# PLCC-RP2350B-PSRAM.net
KiCad netlist of a schematic drawn in Altium Designer
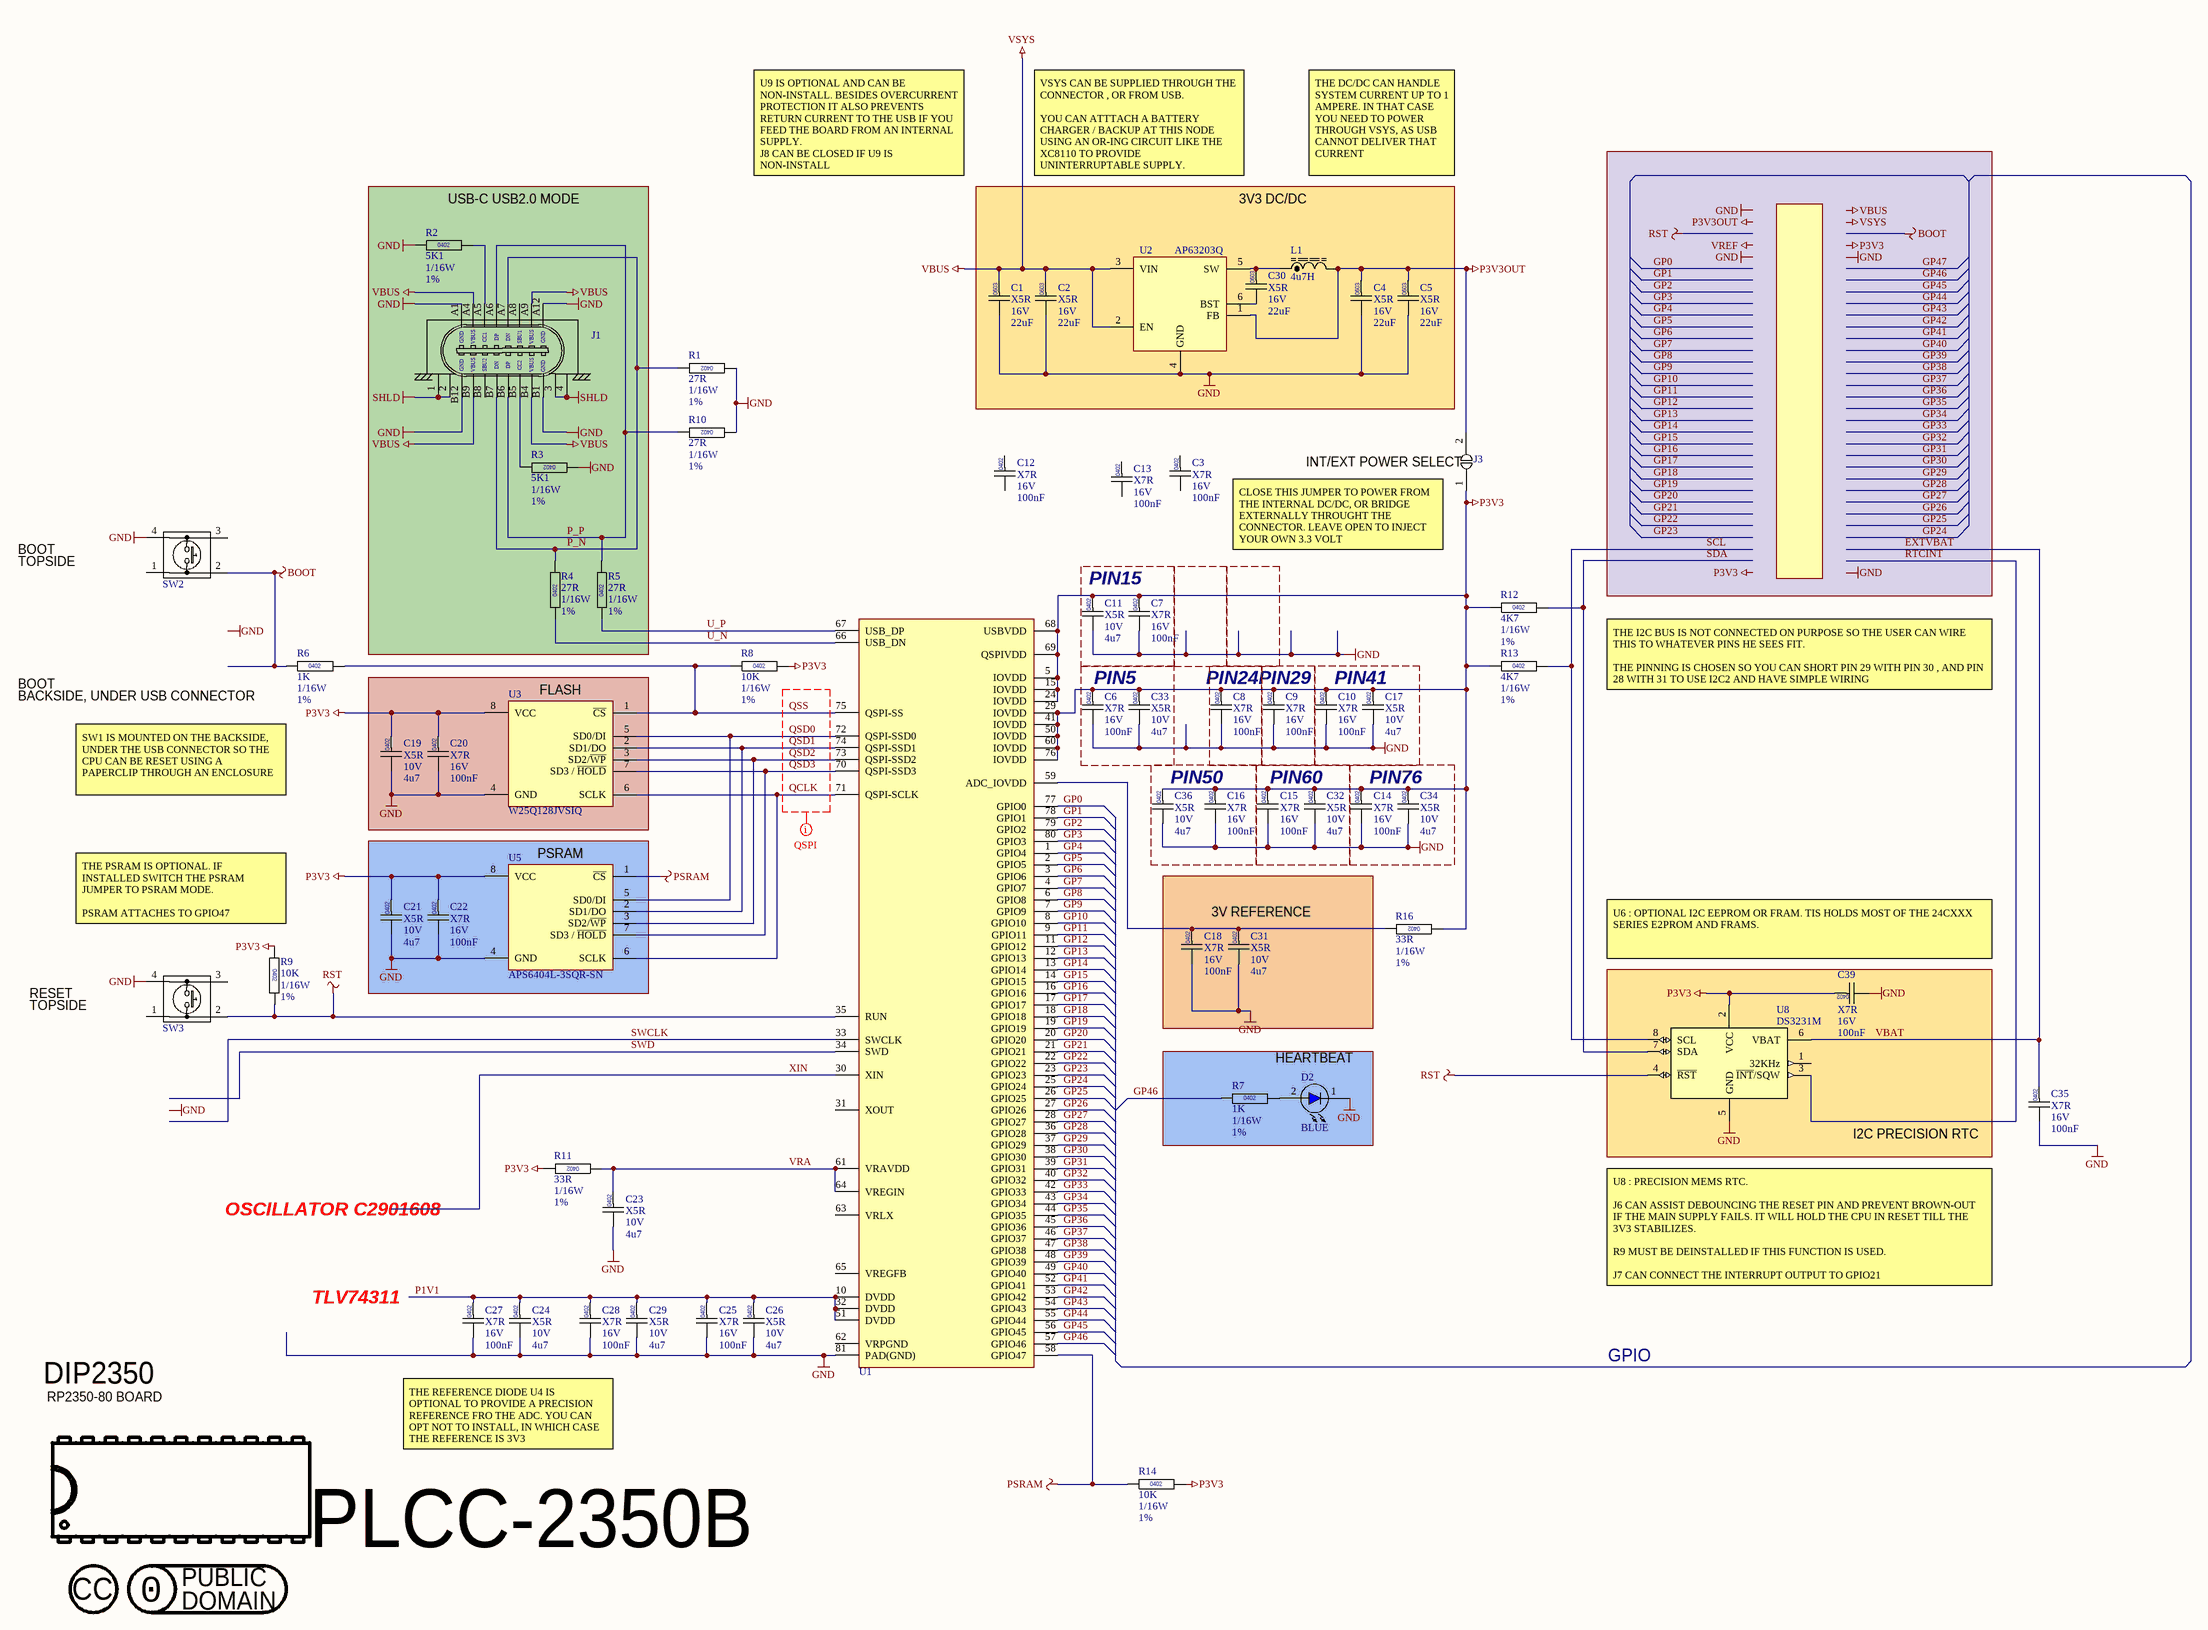
[diagram p0: PLCC-RP2350B-PSRAM.SchDoc]

(export (version "E")
  (design (tool "Eeschema 10.0.6"))
  (components
    (comp (ref "C1")
      (value "CAP0603")
      (footprint "CAPC0603")
      (description "CAPACITOR,CERAMIC,22uF,16V,X5R,0603")
      (fields
        (field (name "DIELECTRIC") "X5R")
        (field (name "VOLTAGE") "16V")
        (field (name "CAPACITANCE") "22uF")
      )
      (libsource (lib "CAPACITORS") (part "CAPC-0603-22uF-16V-X5R"))
    )
    (comp (ref "C2")
      (value "CAP0603")
      (footprint "CAPC0603")
      (description "CAPACITOR,CERAMIC,22uF,16V,X5R,0603")
      (fields
        (field (name "DIELECTRIC") "X5R")
        (field (name "VOLTAGE") "16V")
        (field (name "CAPACITANCE") "22uF")
      )
      (libsource (lib "CAPACITORS") (part "CAPC-0603-22uF-16V-X5R"))
    )
    (comp (ref "C3")
      (value "CAP0402")
      (footprint "CAPC0402")
      (description "CAPACITOR,CERAMIC,100nF,16V,X7R,0402")
      (fields
        (field (name "DIELECTRIC") "X7R")
        (field (name "VOLTAGE") "16V")
        (field (name "CAPACITANCE") "100nF")
      )
      (libsource (lib "CAPACITORS") (part "CAPC-0402-100nF-16V-X7R"))
    )
    (comp (ref "C4")
      (value "CAP0603")
      (footprint "CAPC0603")
      (description "CAPACITOR,CERAMIC,22uF,16V,X5R,0603")
      (fields
        (field (name "DIELECTRIC") "X5R")
        (field (name "VOLTAGE") "16V")
        (field (name "CAPACITANCE") "22uF")
      )
      (libsource (lib "CAPACITORS") (part "CAPC-0603-22uF-16V-X5R"))
    )
    (comp (ref "C5")
      (value "CAP0603")
      (footprint "CAPC0603")
      (description "CAPACITOR,CERAMIC,22uF,16V,X5R,0603")
      (fields
        (field (name "DIELECTRIC") "X5R")
        (field (name "VOLTAGE") "16V")
        (field (name "CAPACITANCE") "22uF")
      )
      (libsource (lib "CAPACITORS") (part "CAPC-0603-22uF-16V-X5R"))
    )
    (comp (ref "C6")
      (value "CAP0402")
      (footprint "CAPC0402")
      (description "CAPACITOR,CERAMIC,100nF,16V,X7R,0402")
      (fields
        (field (name "DIELECTRIC") "X7R")
        (field (name "VOLTAGE") "16V")
        (field (name "CAPACITANCE") "100nF")
      )
      (libsource (lib "CAPACITORS") (part "CAPC-0402-100nF-16V-X7R"))
    )
    (comp (ref "C7")
      (value "CAP0402")
      (footprint "CAPC0402")
      (description "CAPACITOR,CERAMIC,100nF,16V,X7R,0402")
      (fields
        (field (name "DIELECTRIC") "X7R")
        (field (name "VOLTAGE") "16V")
        (field (name "CAPACITANCE") "100nF")
      )
      (libsource (lib "CAPACITORS") (part "CAPC-0402-100nF-16V-X7R"))
    )
    (comp (ref "C8")
      (value "CAP0402")
      (footprint "CAPC0402")
      (description "CAPACITOR,CERAMIC,100nF,16V,X7R,0402")
      (fields
        (field (name "DIELECTRIC") "X7R")
        (field (name "VOLTAGE") "16V")
        (field (name "CAPACITANCE") "100nF")
      )
      (libsource (lib "CAPACITORS") (part "CAPC-0402-100nF-16V-X7R"))
    )
    (comp (ref "C9")
      (value "CAP0402")
      (footprint "CAPC0402")
      (description "CAPACITOR,CERAMIC,100nF,16V,X7R,0402")
      (fields
        (field (name "DIELECTRIC") "X7R")
        (field (name "VOLTAGE") "16V")
        (field (name "CAPACITANCE") "100nF")
      )
      (libsource (lib "CAPACITORS") (part "CAPC-0402-100nF-16V-X7R"))
    )
    (comp (ref "C10")
      (value "CAP0402")
      (footprint "CAPC0402")
      (description "CAPACITOR,CERAMIC,100nF,16V,X7R,0402")
      (fields
        (field (name "DIELECTRIC") "X7R")
        (field (name "VOLTAGE") "16V")
        (field (name "CAPACITANCE") "100nF")
      )
      (libsource (lib "CAPACITORS") (part "CAPC-0402-100nF-16V-X7R"))
    )
    (comp (ref "C11")
      (value "CAP0402")
      (footprint "CAPC0402")
      (description "CAPACITOR,CERAMIC,4u7,10V,X5R,0402")
      (fields
        (field (name "DIELECTRIC") "X5R")
        (field (name "VOLTAGE") "10V")
        (field (name "CAPACITANCE") "4u7")
      )
      (libsource (lib "CAPACITORS") (part "CAPC-0402-4u7-10V-X5R"))
    )
    (comp (ref "C12")
      (value "CAP0402")
      (footprint "CAPC0402")
      (description "CAPACITOR,CERAMIC,100nF,16V,X7R,0402")
      (fields
        (field (name "DIELECTRIC") "X7R")
        (field (name "VOLTAGE") "16V")
        (field (name "CAPACITANCE") "100nF")
      )
      (libsource (lib "CAPACITORS") (part "CAPC-0402-100nF-16V-X7R"))
    )
    (comp (ref "C13")
      (value "CAP0402")
      (footprint "CAPC0402")
      (description "CAPACITOR,CERAMIC,100nF,16V,X7R,0402")
      (fields
        (field (name "DIELECTRIC") "X7R")
        (field (name "VOLTAGE") "16V")
        (field (name "CAPACITANCE") "100nF")
      )
      (libsource (lib "CAPACITORS") (part "CAPC-0402-100nF-16V-X7R"))
    )
    (comp (ref "C14")
      (value "CAP0402")
      (footprint "CAPC0402")
      (description "CAPACITOR,CERAMIC,100nF,16V,X7R,0402")
      (fields
        (field (name "DIELECTRIC") "X7R")
        (field (name "VOLTAGE") "16V")
        (field (name "CAPACITANCE") "100nF")
      )
      (libsource (lib "CAPACITORS") (part "CAPC-0402-100nF-16V-X7R"))
    )
    (comp (ref "C15")
      (value "CAP0402")
      (footprint "CAPC0402")
      (description "CAPACITOR,CERAMIC,100nF,16V,X7R,0402")
      (fields
        (field (name "DIELECTRIC") "X7R")
        (field (name "VOLTAGE") "16V")
        (field (name "CAPACITANCE") "100nF")
      )
      (libsource (lib "CAPACITORS") (part "CAPC-0402-100nF-16V-X7R"))
    )
    (comp (ref "C16")
      (value "CAP0402")
      (footprint "CAPC0402")
      (description "CAPACITOR,CERAMIC,100nF,16V,X7R,0402")
      (fields
        (field (name "DIELECTRIC") "X7R")
        (field (name "VOLTAGE") "16V")
        (field (name "CAPACITANCE") "100nF")
      )
      (libsource (lib "CAPACITORS") (part "CAPC-0402-100nF-16V-X7R"))
    )
    (comp (ref "C17")
      (value "CAP0402")
      (footprint "CAPC0402")
      (description "CAPACITOR,CERAMIC,4u7,10V,X5R,0402")
      (fields
        (field (name "DIELECTRIC") "X5R")
        (field (name "VOLTAGE") "10V")
        (field (name "CAPACITANCE") "4u7")
      )
      (libsource (lib "CAPACITORS") (part "CAPC-0402-4u7-10V-X5R"))
    )
    (comp (ref "C18")
      (value "CAP0402")
      (footprint "CAPC0402")
      (description "CAPACITOR,CERAMIC,100nF,16V,X7R,0402")
      (fields
        (field (name "DIELECTRIC") "X7R")
        (field (name "VOLTAGE") "16V")
        (field (name "CAPACITANCE") "100nF")
      )
      (libsource (lib "CAPACITORS") (part "CAPC-0402-100nF-16V-X7R"))
    )
    (comp (ref "C19")
      (value "CAP0402")
      (footprint "CAPC0402")
      (description "CAPACITOR,CERAMIC,4u7,10V,X5R,0402")
      (fields
        (field (name "DIELECTRIC") "X5R")
        (field (name "VOLTAGE") "10V")
        (field (name "CAPACITANCE") "4u7")
      )
      (libsource (lib "CAPACITORS") (part "CAPC-0402-4u7-10V-X5R"))
    )
    (comp (ref "C20")
      (value "CAP0402")
      (footprint "CAPC0402")
      (description "CAPACITOR,CERAMIC,100nF,16V,X7R,0402")
      (fields
        (field (name "DIELECTRIC") "X7R")
        (field (name "VOLTAGE") "16V")
        (field (name "CAPACITANCE") "100nF")
      )
      (libsource (lib "CAPACITORS") (part "CAPC-0402-100nF-16V-X7R"))
    )
    (comp (ref "C21")
      (value "CAP0402")
      (footprint "CAPC0402")
      (description "CAPACITOR,CERAMIC,4u7,10V,X5R,0402")
      (fields
        (field (name "DIELECTRIC") "X5R")
        (field (name "VOLTAGE") "10V")
        (field (name "CAPACITANCE") "4u7")
      )
      (libsource (lib "CAPACITORS") (part "CAPC-0402-4u7-10V-X5R"))
    )
    (comp (ref "C22")
      (value "CAP0402")
      (footprint "CAPC0402")
      (description "CAPACITOR,CERAMIC,100nF,16V,X7R,0402")
      (fields
        (field (name "DIELECTRIC") "X7R")
        (field (name "VOLTAGE") "16V")
        (field (name "CAPACITANCE") "100nF")
      )
      (libsource (lib "CAPACITORS") (part "CAPC-0402-100nF-16V-X7R"))
    )
    (comp (ref "C23")
      (value "CAP0402")
      (footprint "CAPC0402")
      (description "CAPACITOR,CERAMIC,4u7,10V,X5R,0402")
      (fields
        (field (name "DIELECTRIC") "X5R")
        (field (name "VOLTAGE") "10V")
        (field (name "CAPACITANCE") "4u7")
      )
      (libsource (lib "CAPACITORS") (part "CAPC-0402-4u7-10V-X5R"))
    )
    (comp (ref "C24")
      (value "CAP0402")
      (footprint "CAPC0402")
      (description "CAPACITOR,CERAMIC,4u7,10V,X5R,0402")
      (fields
        (field (name "DIELECTRIC") "X5R")
        (field (name "VOLTAGE") "10V")
        (field (name "CAPACITANCE") "4u7")
      )
      (libsource (lib "CAPACITORS") (part "CAPC-0402-4u7-10V-X5R"))
    )
    (comp (ref "C25")
      (value "CAP0402")
      (footprint "CAPC0402")
      (description "CAPACITOR,CERAMIC,100nF,16V,X7R,0402")
      (fields
        (field (name "DIELECTRIC") "X7R")
        (field (name "VOLTAGE") "16V")
        (field (name "CAPACITANCE") "100nF")
      )
      (libsource (lib "CAPACITORS") (part "CAPC-0402-100nF-16V-X7R"))
    )
    (comp (ref "C26")
      (value "CAP0402")
      (footprint "CAPC0402")
      (description "CAPACITOR,CERAMIC,4u7,10V,X5R,0402")
      (fields
        (field (name "DIELECTRIC") "X5R")
        (field (name "VOLTAGE") "10V")
        (field (name "CAPACITANCE") "4u7")
      )
      (libsource (lib "CAPACITORS") (part "CAPC-0402-4u7-10V-X5R"))
    )
    (comp (ref "C27")
      (value "CAP0402")
      (footprint "CAPC0402")
      (description "CAPACITOR,CERAMIC,100nF,16V,X7R,0402")
      (fields
        (field (name "DIELECTRIC") "X7R")
        (field (name "VOLTAGE") "16V")
        (field (name "CAPACITANCE") "100nF")
      )
      (libsource (lib "CAPACITORS") (part "CAPC-0402-100nF-16V-X7R"))
    )
    (comp (ref "C28")
      (value "CAP0402")
      (footprint "CAPC0402")
      (description "CAPACITOR,CERAMIC,100nF,16V,X7R,0402")
      (fields
        (field (name "DIELECTRIC") "X7R")
        (field (name "VOLTAGE") "16V")
        (field (name "CAPACITANCE") "100nF")
      )
      (libsource (lib "CAPACITORS") (part "CAPC-0402-100nF-16V-X7R"))
    )
    (comp (ref "C29")
      (value "CAP0402")
      (footprint "CAPC0402")
      (description "CAPACITOR,CERAMIC,4u7,10V,X5R,0402")
      (fields
        (field (name "DIELECTRIC") "X5R")
        (field (name "VOLTAGE") "10V")
        (field (name "CAPACITANCE") "4u7")
      )
      (libsource (lib "CAPACITORS") (part "CAPC-0402-4u7-10V-X5R"))
    )
    (comp (ref "C30")
      (value "CAP0603")
      (footprint "CAPC0603")
      (description "CAPACITOR,CERAMIC,22uF,16V,X5R,0603")
      (fields
        (field (name "DIELECTRIC") "X5R")
        (field (name "VOLTAGE") "16V")
        (field (name "CAPACITANCE") "22uF")
      )
      (libsource (lib "CAPACITORS") (part "CAPC-0603-22uF-16V-X5R"))
    )
    (comp (ref "C31")
      (value "CAP0402")
      (footprint "CAPC0402")
      (description "CAPACITOR,CERAMIC,4u7,10V,X5R,0402")
      (fields
        (field (name "DIELECTRIC") "X5R")
        (field (name "VOLTAGE") "10V")
        (field (name "CAPACITANCE") "4u7")
      )
      (libsource (lib "CAPACITORS") (part "CAPC-0402-4u7-10V-X5R"))
    )
    (comp (ref "C32")
      (value "CAP0402")
      (footprint "CAPC0402")
      (description "CAPACITOR,CERAMIC,4u7,10V,X5R,0402")
      (fields
        (field (name "DIELECTRIC") "X5R")
        (field (name "VOLTAGE") "10V")
        (field (name "CAPACITANCE") "4u7")
      )
      (libsource (lib "CAPACITORS") (part "CAPC-0402-4u7-10V-X5R"))
    )
    (comp (ref "C33")
      (value "CAP0402")
      (footprint "CAPC0402")
      (description "CAPACITOR,CERAMIC,4u7,10V,X5R,0402")
      (fields
        (field (name "DIELECTRIC") "X5R")
        (field (name "VOLTAGE") "10V")
        (field (name "CAPACITANCE") "4u7")
      )
      (libsource (lib "CAPACITORS") (part "CAPC-0402-4u7-10V-X5R"))
    )
    (comp (ref "C34")
      (value "CAP0402")
      (footprint "CAPC0402")
      (description "CAPACITOR,CERAMIC,4u7,10V,X5R,0402")
      (fields
        (field (name "DIELECTRIC") "X5R")
        (field (name "VOLTAGE") "10V")
        (field (name "CAPACITANCE") "4u7")
      )
      (libsource (lib "CAPACITORS") (part "CAPC-0402-4u7-10V-X5R"))
    )
    (comp (ref "C35")
      (value "CAP0402")
      (footprint "CAPC0402")
      (description "CAPACITOR,CERAMIC,100nF,16V,X7R,0402")
      (fields
        (field (name "DIELECTRIC") "X7R")
        (field (name "VOLTAGE") "16V")
        (field (name "CAPACITANCE") "100nF")
      )
      (libsource (lib "CAPACITORS") (part "CAPC-0402-100nF-16V-X7R"))
    )
    (comp (ref "C36")
      (value "CAP0402")
      (footprint "CAPC0402")
      (description "CAPACITOR,CERAMIC,4u7,10V,X5R,0402")
      (fields
        (field (name "DIELECTRIC") "X5R")
        (field (name "VOLTAGE") "10V")
        (field (name "CAPACITANCE") "4u7")
      )
      (libsource (lib "CAPACITORS") (part "CAPC-0402-4u7-10V-X5R"))
    )
    (comp (ref "C39")
      (value "CAP0402")
      (footprint "CAPC0402")
      (description "CAPACITOR,CERAMIC,100nF,16V,X7R,0402")
      (fields
        (field (name "DIELECTRIC") "X7R")
        (field (name "VOLTAGE") "16V")
        (field (name "CAPACITANCE") "100nF")
      )
      (libsource (lib "CAPACITORS") (part "CAPC-0402-100nF-16V-X7R"))
    )
    (comp (ref "D2")
      (value "BLUE")
      (footprint "LED-0603-BLUE")
      (description "LED,BLUE,0603")
      (libsource (lib "LED") (part "LED-WURTH-150060BS75000"))
    )
    (comp (ref "J1")
      (value "CONN-USBC-USB2-HOR")
      (footprint "CONN-GCT-USB4085")
      (description "CONN,USB-C,16P,RA,TH,8.94X9.17")
      (libsource (lib "CONNECTORS") (part "CONN-USBC-USB2-HOR"))
    )
    (comp (ref "J3")
      (value "SOLDERPAD-2")
      (footprint "SOLDERPAD-2")
      (libsource (lib "BOARDFEATURES") (part "SOLDERPAD-2"))
    )
    (comp (ref "L1")
      (value "4u7H")
      (footprint "IND-ABRACON-ASPI-3012S-3R9N-T")
      (description "IND,4.7uH,1.06A,3X3, NRH3012T4R7MN")
      (fields (field (name "Comment") "4.7uH"))
      (libsource (lib "INDUCTORS") (part "IND-TAIYO-NRH3012T4R7MN"))
    )
    (comp (ref "LOGO1")
      (value "LOGO-LICENSE-CC0-PUBLIC")
      (footprint "LOGO-LICENSE-CC0-PUBLIC")
      (libsource (lib "LOGO") (part "LOGO-LICENSE-CC0-PUBLIC"))
    )
    (comp (ref "LOGO2")
      (value "LOGO-LICENSE-CC")
      (footprint "LOGO-LICENSE-CC")
      (libsource (lib "LOGO") (part "LOGO-LICENSE-CC"))
    )
    (comp (ref "R1")
      (value "27R")
      (footprint "RESC0402")
      (description "RESISTOR,27R,1%,63mW,0402 (1005)")
      (fields
        (field (name "POWER") "1/16W")
        (field (name "TOLERANCE") "1%")
        (field (name "Comment") "RESC0402")
      )
      (libsource (lib "RESISTORS") (part "RESC-0402-27R-1%-1/10W"))
    )
    (comp (ref "R2")
      (value "5K1")
      (footprint "RESC0402")
      (description "RESISTOR,5K1,1%,63mW,0402 (1005)")
      (fields
        (field (name "POWER") "1/16W")
        (field (name "TOLERANCE") "1%")
        (field (name "Comment") "RESC0402")
      )
      (libsource (lib "RESISTORS") (part "RESC-0402-5K1-1%-1/10W"))
    )
    (comp (ref "R3")
      (value "5K1")
      (footprint "RESC0402")
      (description "RESISTOR,5K1,1%,63mW,0402 (1005)")
      (fields
        (field (name "POWER") "1/16W")
        (field (name "TOLERANCE") "1%")
        (field (name "Comment") "RESC0402")
      )
      (libsource (lib "RESISTORS") (part "RESC-0402-5K1-1%-1/10W"))
    )
    (comp (ref "R4")
      (value "27R")
      (footprint "RESC0402")
      (description "RESISTOR,27R,1%,63mW,0402 (1005)")
      (fields
        (field (name "POWER") "1/16W")
        (field (name "TOLERANCE") "1%")
        (field (name "Comment") "RESC0402")
      )
      (libsource (lib "RESISTORS") (part "RESC-0402-27R-1%-1/10W"))
    )
    (comp (ref "R5")
      (value "27R")
      (footprint "RESC0402")
      (description "RESISTOR,27R,1%,63mW,0402 (1005)")
      (fields
        (field (name "POWER") "1/16W")
        (field (name "TOLERANCE") "1%")
        (field (name "Comment") "RESC0402")
      )
      (libsource (lib "RESISTORS") (part "RESC-0402-27R-1%-1/10W"))
    )
    (comp (ref "R6")
      (value "1K")
      (footprint "RESC0402")
      (description "RESISTOR,1K,1%,63mW,0402 (1005)")
      (fields
        (field (name "POWER") "1/16W")
        (field (name "TOLERANCE") "1%")
        (field (name "Comment") "RESC0402")
      )
      (libsource (lib "RESISTORS") (part "RESC-0402-1K-1%-1/10W"))
    )
    (comp (ref "R7")
      (value "1K")
      (footprint "RESC0402")
      (description "RESISTOR,1K,1%,63mW,0402 (1005)")
      (fields
        (field (name "POWER") "1/16W")
        (field (name "TOLERANCE") "1%")
        (field (name "Comment") "RESC0402")
      )
      (libsource (lib "RESISTORS") (part "RESC-0402-1K-1%-1/10W"))
    )
    (comp (ref "R8")
      (value "10K")
      (footprint "RESC0402")
      (description "RESISTOR,10K,1%,63mW,0402 (1005)")
      (fields
        (field (name "POWER") "1/16W")
        (field (name "TOLERANCE") "1%")
        (field (name "Comment") "RESC0402")
      )
      (libsource (lib "RESISTORS") (part "RESC-0402-10K-1%-1/10W"))
    )
    (comp (ref "R9")
      (value "10K")
      (footprint "RESC0402")
      (description "RESISTOR,10K,1%,63mW,0402 (1005)")
      (fields
        (field (name "POWER") "1/16W")
        (field (name "TOLERANCE") "1%")
        (field (name "Comment") "RESC0402")
      )
      (libsource (lib "RESISTORS") (part "RESC-0402-10K-1%-1/10W"))
    )
    (comp (ref "R10")
      (value "27R")
      (footprint "RESC0402")
      (description "RESISTOR,27R,1%,63mW,0402 (1005)")
      (fields
        (field (name "POWER") "1/16W")
        (field (name "TOLERANCE") "1%")
        (field (name "Comment") "RESC0402")
      )
      (libsource (lib "RESISTORS") (part "RESC-0402-27R-1%-1/10W"))
    )
    (comp (ref "R11")
      (value "33R")
      (footprint "RESC0402")
      (description "RESISTOR,33R,1%,63mW,0402 (1005)")
      (fields
        (field (name "POWER") "1/16W")
        (field (name "TOLERANCE") "1%")
        (field (name "Comment") "RESC0402")
      )
      (libsource (lib "RESISTORS") (part "RESC-0402-33R-1%-1/10W"))
    )
    (comp (ref "R12")
      (value "4K7")
      (footprint "RESC0402")
      (description "RESISTOR,4K7,1%,63mW,0402 (1005)")
      (fields
        (field (name "POWER") "1/16W")
        (field (name "TOLERANCE") "1%")
        (field (name "Comment") "RESC0402")
      )
      (libsource (lib "RESISTORS") (part "RESC-0402-4K7-1%-1/10W"))
    )
    (comp (ref "R13")
      (value "4K7")
      (footprint "RESC0402")
      (description "RESISTOR,4K7,1%,63mW,0402 (1005)")
      (fields
        (field (name "POWER") "1/16W")
        (field (name "TOLERANCE") "1%")
        (field (name "Comment") "RESC0402")
      )
      (libsource (lib "RESISTORS") (part "RESC-0402-4K7-1%-1/10W"))
    )
    (comp (ref "R14")
      (value "10K")
      (footprint "RESC0402")
      (description "RESISTOR,10K,1%,63mW,0402 (1005)")
      (fields
        (field (name "POWER") "1/16W")
        (field (name "TOLERANCE") "1%")
        (field (name "Comment") "RESC0402")
      )
      (libsource (lib "RESISTORS") (part "RESC-0402-10K-1%-1/10W"))
    )
    (comp (ref "R16")
      (value "33R")
      (footprint "RESC0402")
      (description "RESISTOR,33R,1%,63mW,0402 (1005)")
      (fields
        (field (name "POWER") "1/16W")
        (field (name "TOLERANCE") "1%")
        (field (name "Comment") "RESC0402")
      )
      (libsource (lib "RESISTORS") (part "RESC-0402-33R-1%-1/10W"))
    )
    (comp (ref "SW2")
      (value "SWITCH-PANASONIC-EVP-AA202K")
      (footprint "SWITCH-PANASONIC-EVP-AA202K")
      (description "SW,SMD,TACT,4PIN,2.9X3.5,4PIN")
      (libsource (lib "SWITCH") (part "SWITCH-PANASONIC-EVP-AA202K"))
    )
    (comp (ref "SW3")
      (value "SWITCH-PANASONIC-EVP-AA202K")
      (footprint "SWITCH-PANASONIC-EVP-AA202K")
      (description "SW,SMD,TACT,4PIN,2.9X3.5,4PIN")
      (libsource (lib "SWITCH") (part "SWITCH-PANASONIC-EVP-AA202K"))
    )
    (comp (ref "U1")
      (value "IC-RP2350-DIP64")
      (footprint "QFN40P1000X1000X90_HS-81N")
      (description "IC,CPU,RP2350B,QFN80")
      (libsource (lib "IC-CPU") (part "IC-RP2350-DIP64"))
    )
    (comp (ref "U2")
      (value "AP63203Q")
      (footprint "SOT23-6")
      (description "IC,PMIC,STEP-DOWN, 2A 3.3V")
      (libsource (lib "IC-REG") (part "IC-DIODES-AP63203Q"))
    )
    (comp (ref "U3")
      (value "W25Q128JVSIQ")
      (footprint "SO127P790-8N")
      (description "IC,FLASH,QSPI,16Mx8")
      (libsource (lib "IC-SPI") (part "IC-WINBOND-W25Q128JVSIQ"))
    )
    (comp (ref "U5")
      (value "APS6404L-3SQR-SN")
      (footprint "SO127P600-8N")
      (description "IC,PSRAM,QSPI,8Mx8,SO8")
      (libsource (lib "IC-SPI") (part "IC-APMEMORY-APS6404L-3SQR-SN"))
    )
    (comp (ref "U8")
      (value "DS3231M")
      (footprint "SO127P600-8N")
      (description "IC,RTC,I2C,DS3231M")
      (libsource (lib "IC-I2C") (part "IC-ANALOG-DS3231M"))
    )
  )
  (nets
    (net (code "1") (name "/EXTVBAT") (class "Default")
      (node (ref "C35") (pin "1") (pintype "passive"))
      (node (ref "U8") (pin "6") (pinfunction "VBAT_6") (pintype "passive"))
    )
    (net (code "2") (name "/GP0") (class "Default")
      (node (ref "U1") (pin "77") (pinfunction "GPIO0_77") (pintype "passive"))
    )
    (net (code "3") (name "/GP1") (class "Default")
      (node (ref "U1") (pin "78") (pinfunction "GPIO1_78") (pintype "passive"))
    )
    (net (code "4") (name "/GP2") (class "Default")
      (node (ref "U1") (pin "79") (pinfunction "GPIO2_79") (pintype "passive"))
    )
    (net (code "5") (name "/GP3") (class "Default")
      (node (ref "U1") (pin "80") (pinfunction "GPIO3_80") (pintype "passive"))
    )
    (net (code "6") (name "/GP4") (class "Default")
      (node (ref "U1") (pin "1") (pinfunction "GPIO4_1") (pintype "passive"))
    )
    (net (code "7") (name "/GP5") (class "Default")
      (node (ref "U1") (pin "2") (pinfunction "GPIO5_2") (pintype "passive"))
    )
    (net (code "8") (name "/GP6") (class "Default")
      (node (ref "U1") (pin "3") (pinfunction "GPIO6_3") (pintype "passive"))
    )
    (net (code "9") (name "/GP7") (class "Default")
      (node (ref "U1") (pin "4") (pinfunction "GPIO7_4") (pintype "passive"))
    )
    (net (code "10") (name "/GP8") (class "Default")
      (node (ref "U1") (pin "6") (pinfunction "GPIO8_6") (pintype "passive"))
    )
    (net (code "11") (name "/GP9") (class "Default")
      (node (ref "U1") (pin "7") (pinfunction "GPIO9_7") (pintype "passive"))
    )
    (net (code "12") (name "/GP10") (class "Default")
      (node (ref "U1") (pin "8") (pinfunction "GPIO10_8") (pintype "passive"))
    )
    (net (code "13") (name "/GP11") (class "Default")
      (node (ref "U1") (pin "9") (pinfunction "GPIO11_9") (pintype "passive"))
    )
    (net (code "14") (name "/GP12") (class "Default")
      (node (ref "U1") (pin "11") (pinfunction "GPIO12_11") (pintype "passive"))
    )
    (net (code "15") (name "/GP13") (class "Default")
      (node (ref "U1") (pin "12") (pinfunction "GPIO13_12") (pintype "passive"))
    )
    (net (code "16") (name "/GP14") (class "Default")
      (node (ref "U1") (pin "13") (pinfunction "GPIO14_13") (pintype "passive"))
    )
    (net (code "17") (name "/GP15") (class "Default")
      (node (ref "U1") (pin "14") (pinfunction "GPIO15_14") (pintype "passive"))
    )
    (net (code "18") (name "/GP16") (class "Default")
      (node (ref "U1") (pin "16") (pinfunction "GPIO16_16") (pintype "passive"))
    )
    (net (code "19") (name "/GP17") (class "Default")
      (node (ref "U1") (pin "17") (pinfunction "GPIO17_17") (pintype "passive"))
    )
    (net (code "20") (name "/GP18") (class "Default")
      (node (ref "U1") (pin "18") (pinfunction "GPIO18_18") (pintype "passive"))
    )
    (net (code "21") (name "/GP19") (class "Default")
      (node (ref "U1") (pin "19") (pinfunction "GPIO19_19") (pintype "passive"))
    )
    (net (code "22") (name "/GP20") (class "Default")
      (node (ref "U1") (pin "20") (pinfunction "GPIO20_20") (pintype "passive"))
    )
    (net (code "23") (name "/GP21") (class "Default")
      (node (ref "U1") (pin "21") (pinfunction "GPIO21_21") (pintype "passive"))
    )
    (net (code "24") (name "/GP22") (class "Default")
      (node (ref "U1") (pin "22") (pinfunction "GPIO22_22") (pintype "passive"))
    )
    (net (code "25") (name "/GP23") (class "Default")
      (node (ref "U1") (pin "23") (pinfunction "GPIO23_23") (pintype "passive"))
    )
    (net (code "26") (name "/GP24") (class "Default")
      (node (ref "U1") (pin "25") (pinfunction "GPIO24_25") (pintype "passive"))
    )
    (net (code "27") (name "/GP25") (class "Default")
      (node (ref "U1") (pin "26") (pinfunction "GPIO25_26") (pintype "passive"))
    )
    (net (code "28") (name "/GP26") (class "Default")
      (node (ref "U1") (pin "27") (pinfunction "GPIO26_27") (pintype "passive"))
    )
    (net (code "29") (name "/GP27") (class "Default")
      (node (ref "U1") (pin "28") (pinfunction "GPIO27_28") (pintype "passive"))
    )
    (net (code "30") (name "/GP28") (class "Default")
      (node (ref "U1") (pin "36") (pinfunction "GPIO28_36") (pintype "passive"))
    )
    (net (code "31") (name "/GP29") (class "Default")
      (node (ref "U1") (pin "37") (pinfunction "GPIO29_37") (pintype "passive"))
    )
    (net (code "32") (name "/GP30") (class "Default")
      (node (ref "U1") (pin "38") (pinfunction "GPIO30_38") (pintype "passive"))
    )
    (net (code "33") (name "/GP31") (class "Default")
      (node (ref "U1") (pin "39") (pinfunction "GPIO31_39") (pintype "passive"))
    )
    (net (code "34") (name "/GP32") (class "Default")
      (node (ref "U1") (pin "40") (pinfunction "GPIO32_40") (pintype "passive"))
    )
    (net (code "35") (name "/GP33") (class "Default")
      (node (ref "U1") (pin "42") (pinfunction "GPIO33_42") (pintype "passive"))
    )
    (net (code "36") (name "/GP34") (class "Default")
      (node (ref "U1") (pin "43") (pinfunction "GPIO34_43") (pintype "passive"))
    )
    (net (code "37") (name "/GP35") (class "Default")
      (node (ref "U1") (pin "44") (pinfunction "GPIO35_44") (pintype "passive"))
    )
    (net (code "38") (name "/GP36") (class "Default")
      (node (ref "U1") (pin "45") (pinfunction "GPIO36_45") (pintype "passive"))
    )
    (net (code "39") (name "/GP37") (class "Default")
      (node (ref "U1") (pin "46") (pinfunction "GPIO37_46") (pintype "passive"))
    )
    (net (code "40") (name "/GP38") (class "Default")
      (node (ref "U1") (pin "47") (pinfunction "GPIO38_47") (pintype "passive"))
    )
    (net (code "41") (name "/GP39") (class "Default")
      (node (ref "U1") (pin "48") (pinfunction "GPIO39_48") (pintype "passive"))
    )
    (net (code "42") (name "/GP40") (class "Default")
      (node (ref "U1") (pin "49") (pinfunction "GPIO40_49") (pintype "passive"))
    )
    (net (code "43") (name "/GP41") (class "Default")
      (node (ref "U1") (pin "52") (pinfunction "GPIO41_52") (pintype "passive"))
    )
    (net (code "44") (name "/GP42") (class "Default")
      (node (ref "U1") (pin "53") (pinfunction "GPIO42_53") (pintype "passive"))
    )
    (net (code "45") (name "/GP43") (class "Default")
      (node (ref "U1") (pin "54") (pinfunction "GPIO43_54") (pintype "passive"))
    )
    (net (code "46") (name "/GP44") (class "Default")
      (node (ref "U1") (pin "55") (pinfunction "GPIO44_55") (pintype "passive"))
    )
    (net (code "47") (name "/GP45") (class "Default")
      (node (ref "U1") (pin "56") (pinfunction "GPIO45_56") (pintype "passive"))
    )
    (net (code "48") (name "/GP46") (class "Default")
      (node (ref "R7") (pin "1") (pintype "passive"))
      (node (ref "U1") (pin "57") (pinfunction "GPIO46_57") (pintype "passive"))
    )
    (net (code "50") (name "/P1V1") (class "Default")
      (node (ref "C24") (pin "1") (pintype "passive"))
      (node (ref "C25") (pin "1") (pintype "passive"))
      (node (ref "C26") (pin "1") (pintype "passive"))
      (node (ref "C27") (pin "1") (pintype "passive"))
      (node (ref "C28") (pin "1") (pintype "passive"))
      (node (ref "C29") (pin "1") (pintype "passive"))
      (node (ref "U1") (pin "10") (pinfunction "DVDD_10") (pintype "passive"))
      (node (ref "U1") (pin "32") (pinfunction "DVDD_32") (pintype "passive"))
      (node (ref "U1") (pin "51") (pinfunction "DVDD_51") (pintype "passive"))
    )
    (net (code "51") (name "/P_N") (class "Default")
      (node (ref "J1") (pin "A7") (pinfunction "A7_A7") (pintype "passive"))
      (node (ref "J1") (pin "B7") (pinfunction "B7_B7") (pintype "passive"))
      (node (ref "R1") (pin "1") (pintype "passive"))
      (node (ref "R4") (pin "1") (pintype "passive"))
    )
    (net (code "52") (name "/P_P") (class "Default")
      (node (ref "J1") (pin "A6") (pinfunction "A6_A6") (pintype "passive"))
      (node (ref "J1") (pin "B6") (pinfunction "B6_B6") (pintype "passive"))
      (node (ref "R10") (pin "1") (pintype "passive"))
      (node (ref "R5") (pin "1") (pintype "passive"))
    )
    (net (code "53") (name "/QCLK") (class "Default")
      (node (ref "U1") (pin "71") (pinfunction "QSPI-SCLK_71") (pintype "passive"))
      (node (ref "U3") (pin "6") (pinfunction "SCLK_6") (pintype "passive"))
      (node (ref "U5") (pin "6") (pinfunction "SCLK_6") (pintype "passive"))
    )
    (net (code "54") (name "/QSD0") (class "Default")
      (node (ref "U1") (pin "72") (pinfunction "QSPI-SSD0_72") (pintype "passive"))
      (node (ref "U3") (pin "5") (pinfunction "SD0/DI_5") (pintype "passive"))
      (node (ref "U5") (pin "5") (pinfunction "SD0/DI_5") (pintype "passive"))
    )
    (net (code "55") (name "/QSD1") (class "Default")
      (node (ref "U1") (pin "74") (pinfunction "QSPI-SSD1_74") (pintype "passive"))
      (node (ref "U3") (pin "2") (pinfunction "SD1/DO_2") (pintype "passive"))
      (node (ref "U5") (pin "2") (pinfunction "SD1/DO_2") (pintype "passive"))
    )
    (net (code "56") (name "/QSD2") (class "Default")
      (node (ref "U1") (pin "73") (pinfunction "QSPI-SSD2_73") (pintype "passive"))
      (node (ref "U3") (pin "3") (pinfunction "SD2/~{WP}_3") (pintype "passive"))
      (node (ref "U5") (pin "3") (pinfunction "SD2/~{WP}_3") (pintype "passive"))
    )
    (net (code "57") (name "/QSD3") (class "Default")
      (node (ref "U1") (pin "70") (pinfunction "QSPI-SSD3_70") (pintype "passive"))
      (node (ref "U3") (pin "7") (pinfunction "SD3_/_~{HOLD}_7") (pintype "passive"))
      (node (ref "U5") (pin "7") (pinfunction "SD3_/_~{HOLD}_7") (pintype "passive"))
    )
    (net (code "58") (name "/QSS") (class "Default")
      (node (ref "R6") (pin "2") (pintype "passive"))
      (node (ref "R8") (pin "1") (pintype "passive"))
      (node (ref "U1") (pin "75") (pinfunction "QSPI-SS_75") (pintype "passive"))
      (node (ref "U3") (pin "1") (pinfunction "~{CS}_1") (pintype "passive"))
    )
    (net (code "59") (name "/RTCINT") (class "Default")
      (node (ref "U8") (pin "3") (pinfunction "~{INT}/SQW_3") (pintype "output"))
    )
    (net (code "60") (name "/SCL") (class "Default")
      (node (ref "R13") (pin "2") (pintype "passive"))
      (node (ref "U8") (pin "8") (pinfunction "SCL_8") (pintype "bidirectional"))
    )
    (net (code "61") (name "/SDA") (class "Default")
      (node (ref "R12") (pin "2") (pintype "passive"))
      (node (ref "U8") (pin "7") (pinfunction "SDA_7") (pintype "bidirectional"))
    )
    (net (code "62") (name "/SWCLK") (class "Default")
      (node (ref "U1") (pin "33") (pinfunction "SWCLK_33") (pintype "passive"))
    )
    (net (code "63") (name "/SWD") (class "Default")
      (node (ref "U1") (pin "34") (pinfunction "SWD_34") (pintype "passive"))
    )
    (net (code "64") (name "/U_N") (class "Default")
      (node (ref "R4") (pin "2") (pintype "passive"))
      (node (ref "U1") (pin "66") (pinfunction "USB_DN_66") (pintype "passive"))
    )
    (net (code "65") (name "/U_P") (class "Default")
      (node (ref "R5") (pin "2") (pintype "passive"))
      (node (ref "U1") (pin "67") (pinfunction "USB_DP_67") (pintype "passive"))
    )
    (net (code "66") (name "/VRA") (class "Default")
      (node (ref "C23") (pin "1") (pintype "passive"))
      (node (ref "R11") (pin "2") (pintype "passive"))
      (node (ref "U1") (pin "61") (pinfunction "VRAVDD_61") (pintype "passive"))
      (node (ref "U1") (pin "64") (pinfunction "VREGIN_64") (pintype "passive"))
    )
    (net (code "67") (name "/XIN") (class "Default")
      (node (ref "U1") (pin "30") (pinfunction "XIN_30") (pintype "passive"))
    )
    (net (code "68") (name "BOOT") (class "Default")
      (node (ref "R6") (pin "1") (pintype "passive"))
      (node (ref "SW2") (pin "2") (pinfunction "2_2") (pintype "passive"))
    )
    (net (code "69") (name "GND") (class "Default")
      (node (ref "C1") (pin "2") (pintype "passive"))
      (node (ref "C10") (pin "2") (pintype "passive"))
      (node (ref "C11") (pin "2") (pintype "passive"))
      (node (ref "C14") (pin "2") (pintype "passive"))
      (node (ref "C15") (pin "2") (pintype "passive"))
      (node (ref "C16") (pin "2") (pintype "passive"))
      (node (ref "C17") (pin "2") (pintype "passive"))
      (node (ref "C18") (pin "2") (pintype "passive"))
      (node (ref "C19") (pin "2") (pintype "passive"))
      (node (ref "C2") (pin "2") (pintype "passive"))
      (node (ref "C20") (pin "2") (pintype "passive"))
      (node (ref "C21") (pin "2") (pintype "passive"))
      (node (ref "C22") (pin "2") (pintype "passive"))
      (node (ref "C23") (pin "2") (pintype "passive"))
      (node (ref "C24") (pin "2") (pintype "passive"))
      (node (ref "C25") (pin "2") (pintype "passive"))
      (node (ref "C26") (pin "2") (pintype "passive"))
      (node (ref "C27") (pin "2") (pintype "passive"))
      (node (ref "C28") (pin "2") (pintype "passive"))
      (node (ref "C29") (pin "2") (pintype "passive"))
      (node (ref "C31") (pin "2") (pintype "passive"))
      (node (ref "C32") (pin "2") (pintype "passive"))
      (node (ref "C33") (pin "2") (pintype "passive"))
      (node (ref "C34") (pin "2") (pintype "passive"))
      (node (ref "C35") (pin "2") (pintype "passive"))
      (node (ref "C36") (pin "2") (pintype "passive"))
      (node (ref "C39") (pin "2") (pintype "passive"))
      (node (ref "C4") (pin "2") (pintype "passive"))
      (node (ref "C5") (pin "2") (pintype "passive"))
      (node (ref "C6") (pin "2") (pintype "passive"))
      (node (ref "C7") (pin "2") (pintype "passive"))
      (node (ref "C8") (pin "2") (pintype "passive"))
      (node (ref "C9") (pin "2") (pintype "passive"))
      (node (ref "D2") (pin "1") (pinfunction "A_1") (pintype "passive"))
      (node (ref "J1") (pin "A1") (pinfunction "A1_A1") (pintype "passive"))
      (node (ref "J1") (pin "A12") (pinfunction "A12_A12") (pintype "passive"))
      (node (ref "J1") (pin "B1") (pinfunction "B1_B1") (pintype "passive"))
      (node (ref "J1") (pin "B12") (pinfunction "B12_B12") (pintype "passive"))
      (node (ref "R1") (pin "2") (pintype "passive"))
      (node (ref "R10") (pin "2") (pintype "passive"))
      (node (ref "R2") (pin "2") (pintype "passive"))
      (node (ref "R3") (pin "2") (pintype "passive"))
      (node (ref "SW2") (pin "4") (pinfunction "4_4") (pintype "passive"))
      (node (ref "SW3") (pin "4") (pinfunction "4_4") (pintype "passive"))
      (node (ref "U1") (pin "81") (pinfunction "PAD(GND)_81") (pintype "passive"))
      (node (ref "U2") (pin "4") (pinfunction "GND_4") (pintype "passive"))
      (node (ref "U3") (pin "4") (pinfunction "GND_4") (pintype "passive"))
      (node (ref "U5") (pin "4") (pinfunction "GND_4") (pintype "passive"))
      (node (ref "U8") (pin "5") (pinfunction "GND_5") (pintype "power_in"))
    )
    (net (code "70") (name "Net-(D2-K)") (class "Default")
      (node (ref "D2") (pin "2") (pinfunction "K_2") (pintype "passive"))
      (node (ref "R7") (pin "2") (pintype "passive"))
    )
    (net (code "71") (name "Net-(J1-PadA5)") (class "Default")
      (node (ref "J1") (pin "A5") (pinfunction "A5_A5") (pintype "passive"))
      (node (ref "R2") (pin "1") (pintype "passive"))
    )
    (net (code "72") (name "Net-(J1-PadB5)") (class "Default")
      (node (ref "J1") (pin "B5") (pinfunction "B5_B5") (pintype "passive"))
      (node (ref "R3") (pin "1") (pintype "passive"))
    )
    (net (code "73") (name "Net-(U1-ADC_IOVDD)") (class "Default")
      (node (ref "C18") (pin "1") (pintype "passive"))
      (node (ref "C31") (pin "1") (pintype "passive"))
      (node (ref "R16") (pin "1") (pintype "passive"))
      (node (ref "U1") (pin "59") (pinfunction "ADC_IOVDD_59") (pintype "passive"))
    )
    (net (code "74") (name "Net-(U2-BST)") (class "Default")
      (node (ref "C30") (pin "2") (pintype "passive"))
      (node (ref "U2") (pin "6") (pinfunction "BST_6") (pintype "passive"))
    )
    (net (code "75") (name "Net-(U2-SW)") (class "Default")
      (node (ref "C30") (pin "1") (pintype "passive"))
      (node (ref "L1") (pin "1") (pinfunction "1_1") (pintype "passive"))
      (node (ref "U2") (pin "5") (pinfunction "SW_5") (pintype "passive"))
    )
    (net (code "76") (name "P3V3") (class "Default")
      (node (ref "C10") (pin "1") (pintype "passive"))
      (node (ref "C11") (pin "1") (pintype "passive"))
      (node (ref "C14") (pin "1") (pintype "passive"))
      (node (ref "C15") (pin "1") (pintype "passive"))
      (node (ref "C16") (pin "1") (pintype "passive"))
      (node (ref "C17") (pin "1") (pintype "passive"))
      (node (ref "C19") (pin "1") (pintype "passive"))
      (node (ref "C20") (pin "1") (pintype "passive"))
      (node (ref "C21") (pin "1") (pintype "passive"))
      (node (ref "C22") (pin "1") (pintype "passive"))
      (node (ref "C32") (pin "1") (pintype "passive"))
      (node (ref "C33") (pin "1") (pintype "passive"))
      (node (ref "C34") (pin "1") (pintype "passive"))
      (node (ref "C36") (pin "1") (pintype "passive"))
      (node (ref "C39") (pin "1") (pintype "passive"))
      (node (ref "C6") (pin "1") (pintype "passive"))
      (node (ref "C7") (pin "1") (pintype "passive"))
      (node (ref "C8") (pin "1") (pintype "passive"))
      (node (ref "C9") (pin "1") (pintype "passive"))
      (node (ref "J3") (pin "1") (pinfunction "1_1") (pintype "passive"))
      (node (ref "R11") (pin "1") (pintype "passive"))
      (node (ref "R12") (pin "1") (pintype "passive"))
      (node (ref "R13") (pin "1") (pintype "passive"))
      (node (ref "R14") (pin "2") (pintype "passive"))
      (node (ref "R16") (pin "2") (pintype "passive"))
      (node (ref "R8") (pin "2") (pintype "passive"))
      (node (ref "R9") (pin "2") (pintype "passive"))
      (node (ref "U1") (pin "15") (pinfunction "IOVDD_15") (pintype "passive"))
      (node (ref "U1") (pin "24") (pinfunction "IOVDD_24") (pintype "passive"))
      (node (ref "U1") (pin "29") (pinfunction "IOVDD_29") (pintype "passive"))
      (node (ref "U1") (pin "41") (pinfunction "IOVDD_41") (pintype "passive"))
      (node (ref "U1") (pin "5") (pinfunction "IOVDD_5") (pintype "passive"))
      (node (ref "U1") (pin "50") (pinfunction "IOVDD_50") (pintype "passive"))
      (node (ref "U1") (pin "60") (pinfunction "IOVDD_60") (pintype "passive"))
      (node (ref "U1") (pin "68") (pinfunction "USBVDD_68") (pintype "passive"))
      (node (ref "U1") (pin "69") (pinfunction "QSPIVDD_69") (pintype "passive"))
      (node (ref "U1") (pin "76") (pinfunction "IOVDD_76") (pintype "passive"))
      (node (ref "U3") (pin "8") (pinfunction "VCC_8") (pintype "passive"))
      (node (ref "U5") (pin "8") (pinfunction "VCC_8") (pintype "passive"))
      (node (ref "U8") (pin "2") (pinfunction "VCC_2") (pintype "passive"))
    )
    (net (code "77") (name "P3V3OUT") (class "Default")
      (node (ref "C4") (pin "1") (pintype "passive"))
      (node (ref "C5") (pin "1") (pintype "passive"))
      (node (ref "J3") (pin "2") (pinfunction "2_2") (pintype "passive"))
      (node (ref "L1") (pin "2") (pinfunction "2_2") (pintype "passive"))
      (node (ref "U2") (pin "1") (pinfunction "FB_1") (pintype "passive"))
    )
    (net (code "78") (name "PSRAM") (class "Default")
      (node (ref "R14") (pin "1") (pintype "passive"))
      (node (ref "U1") (pin "58") (pinfunction "GPIO47_58") (pintype "passive"))
      (node (ref "U5") (pin "1") (pinfunction "~{CS}_1") (pintype "passive"))
    )
    (net (code "79") (name "RST") (class "Default")
      (node (ref "R9") (pin "1") (pintype "passive"))
      (node (ref "SW3") (pin "2") (pinfunction "2_2") (pintype "passive"))
      (node (ref "U1") (pin "35") (pinfunction "RUN_35") (pintype "passive"))
      (node (ref "U8") (pin "4") (pinfunction "~{RST}_4") (pintype "bidirectional"))
    )
    (net (code "80") (name "SHLD") (class "Default")
      (node (ref "J1") (pin "1") (pinfunction "1_1") (pintype "passive"))
      (node (ref "J1") (pin "2") (pinfunction "2_2") (pintype "passive"))
      (node (ref "J1") (pin "3") (pinfunction "3_3") (pintype "passive"))
      (node (ref "J1") (pin "4") (pinfunction "4_4") (pintype "passive"))
    )
    (net (code "81") (name "VBUS") (class "Default")
      (node (ref "C1") (pin "1") (pintype "passive"))
      (node (ref "C2") (pin "1") (pintype "passive"))
      (node (ref "J1") (pin "A4") (pinfunction "A4_A4") (pintype "passive"))
      (node (ref "J1") (pin "A9") (pinfunction "A9_A9") (pintype "passive"))
      (node (ref "J1") (pin "B4") (pinfunction "B4_B4") (pintype "passive"))
      (node (ref "J1") (pin "B9") (pinfunction "B9_B9") (pintype "passive"))
      (node (ref "U2") (pin "2") (pinfunction "EN_2") (pintype "passive"))
      (node (ref "U2") (pin "3") (pinfunction "VIN_3") (pintype "passive"))
    )
    (net (code "83") (name "unconnected-(C3-Pad1)") (class "Default")
      (node (ref "C3") (pin "1") (pintype "passive"))
    )
    (net (code "84") (name "unconnected-(C3-Pad2)") (class "Default")
      (node (ref "C3") (pin "2") (pintype "passive"))
    )
    (net (code "85") (name "unconnected-(C12-Pad1)") (class "Default")
      (node (ref "C12") (pin "1") (pintype "passive"))
    )
    (net (code "86") (name "unconnected-(C12-Pad2)") (class "Default")
      (node (ref "C12") (pin "2") (pintype "passive"))
    )
    (net (code "87") (name "unconnected-(C13-Pad1)") (class "Default")
      (node (ref "C13") (pin "1") (pintype "passive"))
    )
    (net (code "88") (name "unconnected-(C13-Pad2)") (class "Default")
      (node (ref "C13") (pin "2") (pintype "passive"))
    )
    (net (code "89") (name "unconnected-(J1-PadA8)") (class "Default")
      (node (ref "J1") (pin "A8") (pinfunction "A8_A8") (pintype "passive"))
    )
    (net (code "90") (name "unconnected-(J1-PadB8)") (class "Default")
      (node (ref "J1") (pin "B8") (pinfunction "B8_B8") (pintype "passive"))
    )
    (net (code "91") (name "unconnected-(SW2-Pad1)") (class "Default")
      (node (ref "SW2") (pin "1") (pinfunction "1_1") (pintype "passive"))
    )
    (net (code "92") (name "unconnected-(SW2-Pad3)") (class "Default")
      (node (ref "SW2") (pin "3") (pinfunction "3_3") (pintype "passive"))
    )
    (net (code "93") (name "unconnected-(SW3-Pad1)") (class "Default")
      (node (ref "SW3") (pin "1") (pinfunction "1_1") (pintype "passive"))
    )
    (net (code "94") (name "unconnected-(SW3-Pad3)") (class "Default")
      (node (ref "SW3") (pin "3") (pinfunction "3_3") (pintype "passive"))
    )
    (net (code "95") (name "unconnected-(U1-VREGFB-Pad65)") (class "Default")
      (node (ref "U1") (pin "65") (pinfunction "VREGFB_65") (pintype "passive"))
    )
    (net (code "96") (name "unconnected-(U1-VRLX-Pad63)") (class "Default")
      (node (ref "U1") (pin "63") (pinfunction "VRLX_63") (pintype "passive"))
    )
    (net (code "97") (name "unconnected-(U1-VRPGND-Pad62)") (class "Default")
      (node (ref "U1") (pin "62") (pinfunction "VRPGND_62") (pintype "passive"))
    )
    (net (code "98") (name "unconnected-(U1-XOUT-Pad31)") (class "Default")
      (node (ref "U1") (pin "31") (pinfunction "XOUT_31") (pintype "passive"))
    )
    (net (code "99") (name "unconnected-(U8-32KHz-Pad1)") (class "Default")
      (node (ref "U8") (pin "1") (pinfunction "32KHz_1") (pintype "output"))
    )
  )
)
